# Schema.net
KiCad netlist of a schematic drawn in Altium Designer
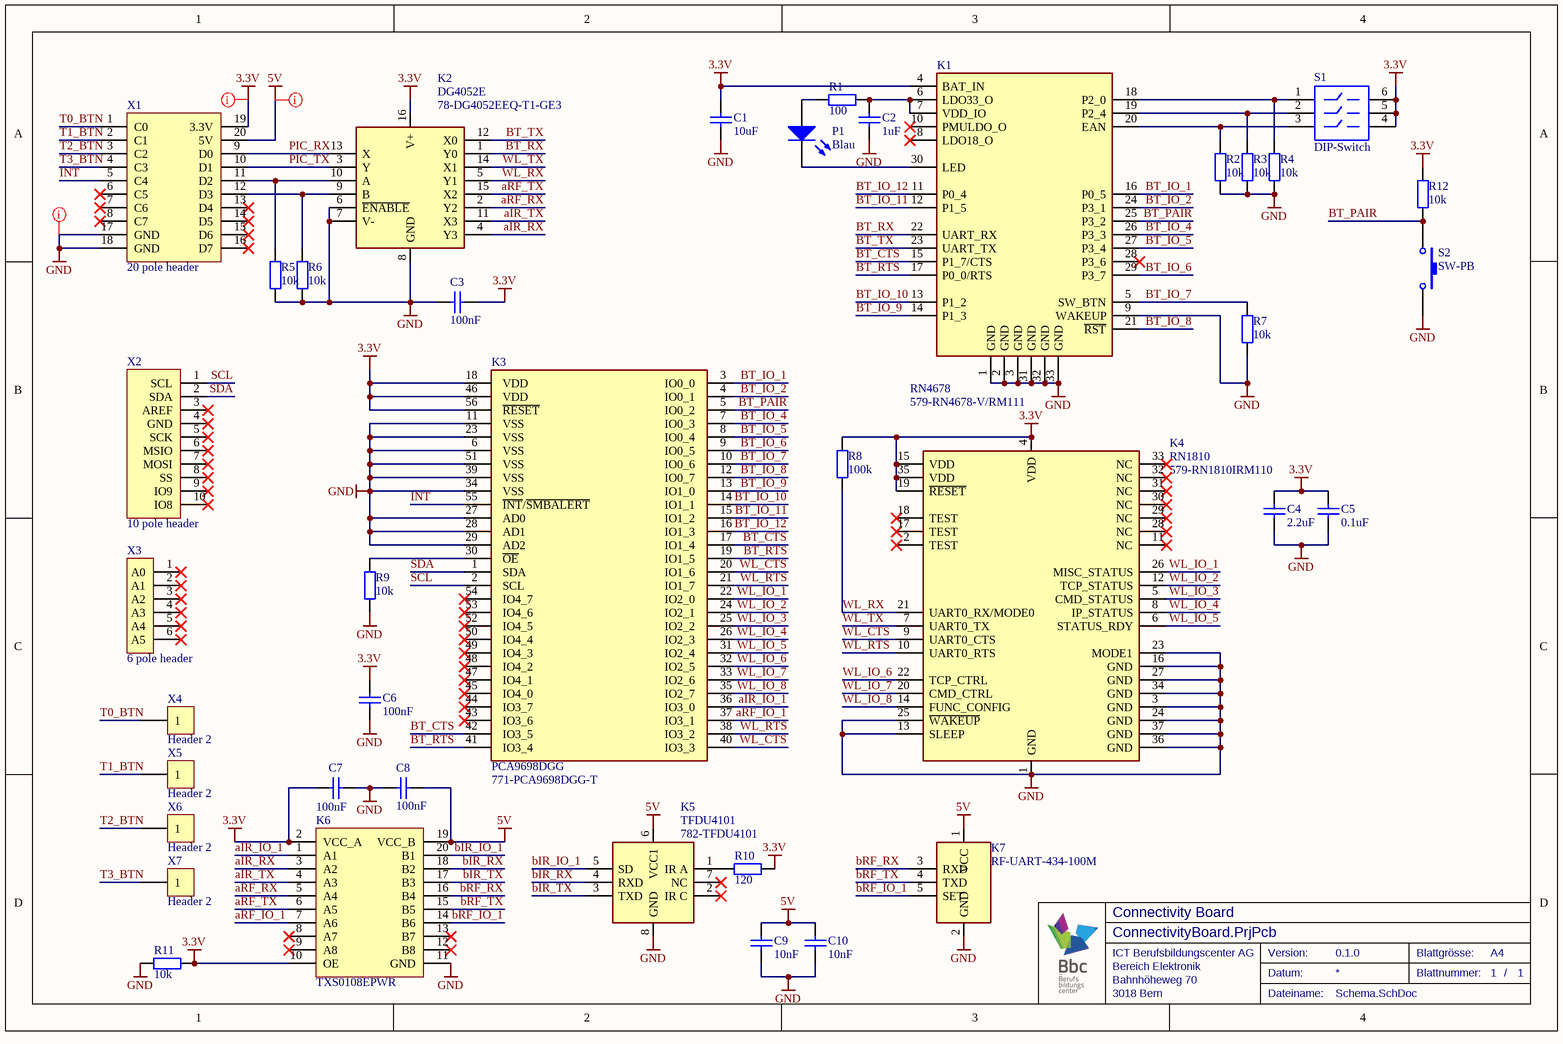
[diagram p0: Schema.SchDoc]

(export (version "E")
  (design (tool "Eeschema 10.0.6"))
  (components
    (comp (ref "C1")
      (value "10uF")
      (footprint "CAP CER 0805 H")
      (description "Non polarized capacitor")
      (fields (field (name "Comment") "Capacitor") (field (name "PUBLISHER") "ICT Berufsbildungscenter AG"))
      (libsource (lib "SchematicLibrary") (part "Capacitor"))
    )
    (comp (ref "C2")
      (value "1uF")
      (footprint "CAP CER 0805 H")
      (description "Non polarized capacitor")
      (fields (field (name "Comment") "Capacitor") (field (name "PUBLISHER") "ICT Berufsbildungscenter AG"))
      (libsource (lib "SchematicLibrary") (part "Capacitor"))
    )
    (comp (ref "C3")
      (value "100nF")
      (footprint "CAP CER 0805 H")
      (description "Non polarized capacitor")
      (fields (field (name "Comment") "Capacitor") (field (name "PUBLISHER") "ICT Berufsbildungscenter AG"))
      (libsource (lib "SchematicLibrary") (part "Capacitor"))
    )
    (comp (ref "C4")
      (value "2.2uF")
      (footprint "CAP CER 0805 H")
      (description "Non polarized capacitor")
      (fields (field (name "Comment") "Capacitor") (field (name "PUBLISHER") "ICT Berufsbildungscenter AG"))
      (libsource (lib "SchematicLibrary") (part "Capacitor"))
    )
    (comp (ref "C5")
      (value "0.1uF")
      (footprint "CAP CER 0805 H")
      (description "Non polarized capacitor")
      (fields (field (name "Comment") "Capacitor") (field (name "PUBLISHER") "ICT Berufsbildungscenter AG"))
      (libsource (lib "SchematicLibrary") (part "Capacitor"))
    )
    (comp (ref "C6")
      (value "100nF")
      (footprint "CAP CER 0805 H")
      (description "Non polarized capacitor")
      (fields (field (name "Comment") "Capacitor") (field (name "PUBLISHER") "ICT Berufsbildungscenter AG"))
      (libsource (lib "SchematicLibrary") (part "Capacitor"))
    )
    (comp (ref "C7")
      (value "100nF")
      (footprint "CAP CER 0805 H")
      (description "Non polarized capacitor")
      (fields (field (name "Comment") "Capacitor") (field (name "PUBLISHER") "ICT Berufsbildungscenter AG"))
      (libsource (lib "SchematicLibrary") (part "Capacitor"))
    )
    (comp (ref "C8")
      (value "100nF")
      (footprint "CAP CER 0805 H")
      (description "Non polarized capacitor")
      (fields (field (name "Comment") "Capacitor") (field (name "PUBLISHER") "ICT Berufsbildungscenter AG"))
      (libsource (lib "SchematicLibrary") (part "Capacitor"))
    )
    (comp (ref "C9")
      (value "10nF")
      (footprint "CAP CER 0805 H")
      (description "Non polarized capacitor")
      (fields (field (name "Comment") "Capacitor") (field (name "PUBLISHER") "ICT Berufsbildungscenter AG"))
      (libsource (lib "SchematicLibrary") (part "Capacitor"))
    )
    (comp (ref "C10")
      (value "10nF")
      (footprint "CAP CER 0805 H")
      (description "Non polarized capacitor")
      (fields (field (name "Comment") "Capacitor") (field (name "PUBLISHER") "ICT Berufsbildungscenter AG"))
      (libsource (lib "SchematicLibrary") (part "Capacitor"))
    )
    (comp (ref "K1")
      (value "RN4678")
      (footprint "RN4678 Bluetooth Modul")
      (fields (field (name "SUPPLIER PART NUMBER 1") "579-RN4678-V/RM111"))
      (libsource (lib "SchematicLibrary") (part "Bluetooth-Modul"))
    )
    (comp (ref "K2")
      (value "DG4052E")
      (footprint "TSSOP-16")
      (description "Analogschalter IC Dual 4 Ch Multiplxr Pd 450mW TSSOP-16")
      (fields (field (name "SUPPLIER PART NUMBER 1") "78-DG4052EEQ-T1-GE3"))
      (libsource (lib "SchematicLibrary") (part "AnalogSwitch"))
    )
    (comp (ref "K3")
      (value "PCA9698DGG")
      (footprint "TSSOP-56")
      (description "Schnittstelle - I/O-Erweiterer 40BT I2C FM+TPGPIO IN-RS-PU OE")
      (fields (field (name "SUPPLIER PART NUMBER 1") "771-PCA9698DGG-T"))
      (libsource (lib "SchematicLibrary") (part "PortExpander"))
    )
    (comp (ref "K4")
      (value "RN1810")
      (footprint "RN1810 WLAN")
      (description "WLAN-Module (802.11) On board WiFiWiFly UART and PCB antenna")
      (fields (field (name "SUPPLIER PART NUMBER 1") "579-RN1810IRM110"))
      (libsource (lib "SchematicLibrary") (part "WLAN-Modul"))
    )
    (comp (ref "K5")
      (value "TFDU4101")
      (footprint "TFDU4101 Infrarot Modul")
      (description "Infrarot-Transceiver SIR 115.2 kbits/s")
      (fields (field (name "SUPPLIER PART NUMBER 1") "782-TFDU4101"))
      (libsource (lib "SchematicLibrary") (part "Infrarot-Modul"))
    )
    (comp (ref "K6")
      (value "TXS0108EPWR")
      (footprint "TSSOP-20 H")
      (description "Level Shifter with internal pullups")
      (libsource (lib "BBC_Components") (part "TXS0108EPWR"))
    )
    (comp (ref "K7")
      (value "RF-UART-434-100M")
      (footprint "RF-UART-434-100M")
      (description "RF-Modul UART/TTL Interface 100M")
      (libsource (lib "SchematicLibrary") (part "RF-Modul"))
    )
    (comp (ref "P1")
      (value "Blau")
      (footprint "LED 1206 blue R")
      (description "Light emitting diode")
      (fields (field (name "PUBLISHER") "ICT Berufsbildungscenter AG"))
      (libsource (lib "SchematicLibrary") (part "LED"))
    )
    (comp (ref "R1")
      (value "100")
      (footprint "RES 0805 H")
      (description "Resistor")
      (fields (field (name "PUBLISHER") "ICT Berufsbildungscenter AG"))
      (libsource (lib "") (part "Resistor_1"))
    )
    (comp (ref "R2")
      (value "10k")
      (footprint "RES 0805 H")
      (description "Resistor")
      (fields (field (name "PUBLISHER") "ICT Berufsbildungscenter AG"))
      (libsource (lib "SchematicLibrary") (part "Resistor"))
    )
    (comp (ref "R3")
      (value "10k")
      (footprint "RES 0805 H")
      (description "Resistor")
      (fields (field (name "PUBLISHER") "ICT Berufsbildungscenter AG"))
      (libsource (lib "SchematicLibrary") (part "Resistor"))
    )
    (comp (ref "R4")
      (value "10k")
      (footprint "RES 0805 H")
      (description "Resistor")
      (fields (field (name "PUBLISHER") "ICT Berufsbildungscenter AG"))
      (libsource (lib "SchematicLibrary") (part "Resistor"))
    )
    (comp (ref "R5")
      (value "10k")
      (footprint "RES 0805 H")
      (description "Resistor")
      (fields (field (name "PUBLISHER") "ICT Berufsbildungscenter AG"))
      (libsource (lib "SchematicLibrary") (part "Resistor"))
    )
    (comp (ref "R6")
      (value "10k")
      (footprint "RES 0805 H")
      (description "Resistor")
      (fields (field (name "PUBLISHER") "ICT Berufsbildungscenter AG"))
      (libsource (lib "SchematicLibrary") (part "Resistor"))
    )
    (comp (ref "R7")
      (value "10k")
      (footprint "RES 0805 H")
      (description "Resistor")
      (fields (field (name "PUBLISHER") "ICT Berufsbildungscenter AG"))
      (libsource (lib "BBC_Components") (part "Resistor"))
    )
    (comp (ref "R8")
      (value "100k")
      (footprint "RES 0805 H")
      (description "Resistor")
      (fields (field (name "PUBLISHER") "ICT Berufsbildungscenter AG"))
      (libsource (lib "BBC_Components") (part "Resistor"))
    )
    (comp (ref "R9")
      (value "10k")
      (footprint "RES 0805 H")
      (description "Resistor")
      (fields (field (name "PUBLISHER") "ICT Berufsbildungscenter AG"))
      (libsource (lib "BBC_Components") (part "Resistor"))
    )
    (comp (ref "R10")
      (value "120")
      (footprint "RES 0805 H")
      (description "Resistor")
      (fields (field (name "PUBLISHER") "ICT Berufsbildungscenter AG"))
      (libsource (lib "") (part "Resistor_1"))
    )
    (comp (ref "R11")
      (value "10k")
      (footprint "RES 0805 H")
      (description "Resistor")
      (fields (field (name "PUBLISHER") "ICT Berufsbildungscenter AG"))
      (libsource (lib "") (part "Resistor_1"))
    )
    (comp (ref "R12")
      (value "10k")
      (footprint "RES 0805 H")
      (description "Resistor")
      (fields (field (name "PUBLISHER") "ICT Berufsbildungscenter AG"))
      (libsource (lib "SchematicLibrary") (part "Resistor"))
    )
    (comp (ref "S1")
      (value "DIP-Switch")
      (footprint "DIP Switch SMD 3 H")
      (description "Dip Switch with 3 switches")
      (fields (field (name "PUBLISHER") "ICT Berufsbildungscenter AG"))
      (libsource (lib "SchematicLibrary") (part "DIP-Switch 3"))
    )
    (comp (ref "S2")
      (value "SW-PB")
      (footprint "drucktaster")
      (description "Switch, SMD")
      (fields (field (name "PUBLISHER") "Altium Limited"))
      (libsource (lib "SchematicLibrary") (part "Drucktaster"))
    )
    (comp (ref "X1")
      (value "20 pole header")
      (footprint "Header THT male 2x10")
      (description "board to board header")
      (fields (field (name "PUBLISHER") "ICT Berufsbildungscenter AG"))
      (libsource (lib "SchematicLibrary") (part "Header 20"))
    )
    (comp (ref "X2")
      (value "10 pole header")
      (footprint "Header THT male 1x10")
      (description "board to board header")
      (fields (field (name "PUBLISHER") "ICT Berufsbildungscenter AG"))
      (libsource (lib "SchematicLibrary") (part "Header 10"))
    )
    (comp (ref "X3")
      (value "6 pole header")
      (footprint "Header THT male 1x6")
      (description "board to board header")
      (fields (field (name "PUBLISHER") "ICT Berufsbildungscenter AG"))
      (libsource (lib "SchematicLibrary") (part "Header 6"))
    )
    (comp (ref "X4")
      (value "Header 2")
      (footprint "TouchPads")
      (description "Header, 2-Pin")
      (fields (field (name "PUBLISHER") "Altium Limited"))
      (libsource (lib "SchematicLibrary") (part "Header 1"))
    )
    (comp (ref "X5")
      (value "Header 2")
      (footprint "TouchPads")
      (description "Header, 2-Pin")
      (fields (field (name "PUBLISHER") "Altium Limited"))
      (libsource (lib "SchematicLibrary") (part "Header 1"))
    )
    (comp (ref "X6")
      (value "Header 2")
      (footprint "TouchPads")
      (description "Header, 2-Pin")
      (fields (field (name "PUBLISHER") "Altium Limited"))
      (libsource (lib "SchematicLibrary") (part "Header 1"))
    )
    (comp (ref "X7")
      (value "Header 2")
      (footprint "TouchPads")
      (description "Header, 2-Pin")
      (fields (field (name "PUBLISHER") "Altium Limited"))
      (libsource (lib "SchematicLibrary") (part "Header 1"))
    )
  )
  (nets
    (net (code "1") (name "/BT_CTS") (class "Default")
      (node (ref "K1") (pin "15") (pinfunction "P1_7/CTS_15") (pintype "passive"))
      (node (ref "K3") (pin "17") (pinfunction "IO1_4_17") (pintype "passive"))
      (node (ref "K3") (pin "42") (pinfunction "IO3_5_42") (pintype "passive"))
    )
    (net (code "2") (name "/BT_IO_1") (class "Default")
      (node (ref "K1") (pin "16") (pinfunction "P0_5_16") (pintype "passive"))
      (node (ref "K3") (pin "3") (pinfunction "IO0_0_3") (pintype "passive"))
    )
    (net (code "3") (name "/BT_IO_2") (class "Default")
      (node (ref "K1") (pin "24") (pinfunction "P3_1_24") (pintype "passive"))
      (node (ref "K3") (pin "4") (pinfunction "IO0_1_4") (pintype "passive"))
    )
    (net (code "4") (name "/BT_IO_4") (class "Default")
      (node (ref "K1") (pin "26") (pinfunction "P3_3_26") (pintype "passive"))
      (node (ref "K3") (pin "7") (pinfunction "IO0_3_7") (pintype "passive"))
    )
    (net (code "5") (name "/BT_IO_5") (class "Default")
      (node (ref "K1") (pin "27") (pinfunction "P3_4_27") (pintype "passive"))
      (node (ref "K3") (pin "8") (pinfunction "IO0_4_8") (pintype "passive"))
    )
    (net (code "6") (name "/BT_IO_6") (class "Default")
      (node (ref "K1") (pin "29") (pinfunction "P3_7_29") (pintype "passive"))
      (node (ref "K3") (pin "9") (pinfunction "IO0_5_9") (pintype "passive"))
    )
    (net (code "7") (name "/BT_IO_7") (class "Default")
      (node (ref "K1") (pin "5") (pinfunction "SW_BTN_5") (pintype "passive"))
      (node (ref "K3") (pin "10") (pinfunction "IO0_6_10") (pintype "passive"))
      (node (ref "R7") (pin "2") (pinfunction "2_2") (pintype "passive"))
    )
    (net (code "8") (name "/BT_IO_8") (class "Default")
      (node (ref "K1") (pin "21") (pinfunction "~{RST}_21") (pintype "passive"))
      (node (ref "K3") (pin "12") (pinfunction "IO0_7_12") (pintype "passive"))
    )
    (net (code "9") (name "/BT_IO_9") (class "Default")
      (node (ref "K1") (pin "14") (pinfunction "P1_3_14") (pintype "passive"))
      (node (ref "K3") (pin "13") (pinfunction "IO1_0_13") (pintype "passive"))
    )
    (net (code "10") (name "/BT_IO_10") (class "Default")
      (node (ref "K1") (pin "13") (pinfunction "P1_2_13") (pintype "passive"))
      (node (ref "K3") (pin "14") (pinfunction "IO1_1_14") (pintype "passive"))
    )
    (net (code "11") (name "/BT_IO_11") (class "Default")
      (node (ref "K1") (pin "12") (pinfunction "P1_5_12") (pintype "passive"))
      (node (ref "K3") (pin "15") (pinfunction "IO1_2_15") (pintype "passive"))
    )
    (net (code "12") (name "/BT_IO_12") (class "Default")
      (node (ref "K1") (pin "11") (pinfunction "P0_4_11") (pintype "passive"))
      (node (ref "K3") (pin "16") (pinfunction "IO1_3_16") (pintype "passive"))
    )
    (net (code "13") (name "/BT_PAIR") (class "Default")
      (node (ref "K1") (pin "25") (pinfunction "P3_2_25") (pintype "passive"))
      (node (ref "K3") (pin "5") (pinfunction "IO0_2_5") (pintype "passive"))
      (node (ref "R12") (pin "1") (pinfunction "1_1") (pintype "passive"))
      (node (ref "S2") (pin "4") (pinfunction "4_4") (pintype "passive"))
    )
    (net (code "14") (name "/BT_RTS") (class "Default")
      (node (ref "K1") (pin "17") (pinfunction "P0_0/RTS_17") (pintype "passive"))
      (node (ref "K3") (pin "19") (pinfunction "IO1_5_19") (pintype "passive"))
      (node (ref "K3") (pin "41") (pinfunction "IO3_4_41") (pintype "passive"))
    )
    (net (code "15") (name "/BT_RX") (class "Default")
      (node (ref "K1") (pin "22") (pinfunction "UART_RX_22") (pintype "passive"))
      (node (ref "K2") (pin "1") (pinfunction "Y0_1") (pintype "passive"))
    )
    (net (code "16") (name "/BT_TX") (class "Default")
      (node (ref "K1") (pin "23") (pinfunction "UART_TX_23") (pintype "passive"))
      (node (ref "K2") (pin "12") (pinfunction "X0_12") (pintype "passive"))
    )
    (net (code "17") (name "/PIC_RX") (class "Default")
      (node (ref "K2") (pin "13") (pinfunction "X_13") (pintype "passive"))
      (node (ref "X1") (pin "9") (pinfunction "D0_9") (pintype "passive"))
    )
    (net (code "18") (name "/PIC_TX") (class "Default")
      (node (ref "K2") (pin "3") (pinfunction "Y_3") (pintype "passive"))
      (node (ref "X1") (pin "10") (pinfunction "D1_10") (pintype "passive"))
    )
    (net (code "19") (name "/SCL") (class "Default")
      (node (ref "K3") (pin "2") (pinfunction "SCL_2") (pintype "passive"))
      (node (ref "X2") (pin "1") (pinfunction "SCL_1") (pintype "passive"))
    )
    (net (code "20") (name "/SDA") (class "Default")
      (node (ref "K3") (pin "1") (pinfunction "SDA_1") (pintype "passive"))
      (node (ref "X2") (pin "2") (pinfunction "SDA_2") (pintype "passive"))
    )
    (net (code "21") (name "/T0_BTN") (class "Default")
      (node (ref "X1") (pin "1") (pinfunction "C0_1") (pintype "passive"))
      (node (ref "X4") (pin "1") (pinfunction "1_1") (pintype "passive"))
    )
    (net (code "22") (name "/T1_BTN") (class "Default")
      (node (ref "X1") (pin "2") (pinfunction "C1_2") (pintype "passive"))
      (node (ref "X5") (pin "1") (pinfunction "1_1") (pintype "passive"))
    )
    (net (code "23") (name "/T2_BTN") (class "Default")
      (node (ref "X1") (pin "3") (pinfunction "C2_3") (pintype "passive"))
      (node (ref "X6") (pin "1") (pinfunction "1_1") (pintype "passive"))
    )
    (net (code "24") (name "/T3_BTN") (class "Default")
      (node (ref "X1") (pin "4") (pinfunction "C3_4") (pintype "passive"))
      (node (ref "X7") (pin "1") (pinfunction "1_1") (pintype "passive"))
    )
    (net (code "25") (name "/WL_CTS") (class "Default")
      (node (ref "K3") (pin "20") (pinfunction "IO1_6_20") (pintype "passive"))
      (node (ref "K3") (pin "40") (pinfunction "IO3_3_40") (pintype "passive"))
      (node (ref "K4") (pin "9") (pinfunction "UART0_CTS_9") (pintype "passive"))
    )
    (net (code "26") (name "/WL_IO_1") (class "Default")
      (node (ref "K3") (pin "22") (pinfunction "IO2_0_22") (pintype "passive"))
      (node (ref "K4") (pin "26") (pinfunction "MISC_STATUS_26") (pintype "passive"))
    )
    (net (code "27") (name "/WL_IO_2") (class "Default")
      (node (ref "K3") (pin "24") (pinfunction "IO2_1_24") (pintype "passive"))
      (node (ref "K4") (pin "12") (pinfunction "TCP_STATUS_12") (pintype "passive"))
    )
    (net (code "28") (name "/WL_IO_3") (class "Default")
      (node (ref "K3") (pin "25") (pinfunction "IO2_2_25") (pintype "passive"))
      (node (ref "K4") (pin "5") (pinfunction "CMD_STATUS_5") (pintype "passive"))
    )
    (net (code "29") (name "/WL_IO_4") (class "Default")
      (node (ref "K3") (pin "26") (pinfunction "IO2_3_26") (pintype "passive"))
      (node (ref "K4") (pin "8") (pinfunction "IP_STATUS_8") (pintype "passive"))
    )
    (net (code "30") (name "/WL_IO_5") (class "Default")
      (node (ref "K3") (pin "31") (pinfunction "IO2_4_31") (pintype "passive"))
      (node (ref "K4") (pin "6") (pinfunction "STATUS_RDY_6") (pintype "passive"))
    )
    (net (code "31") (name "/WL_IO_6") (class "Default")
      (node (ref "K3") (pin "32") (pinfunction "IO2_5_32") (pintype "passive"))
      (node (ref "K4") (pin "22") (pinfunction "TCP_CTRL_22") (pintype "passive"))
    )
    (net (code "32") (name "/WL_IO_7") (class "Default")
      (node (ref "K3") (pin "33") (pinfunction "IO2_6_33") (pintype "passive"))
      (node (ref "K4") (pin "20") (pinfunction "CMD_CTRL_20") (pintype "passive"))
    )
    (net (code "33") (name "/WL_IO_8") (class "Default")
      (node (ref "K3") (pin "35") (pinfunction "IO2_7_35") (pintype "passive"))
      (node (ref "K4") (pin "14") (pinfunction "FUNC_CONFIG_14") (pintype "passive"))
    )
    (net (code "34") (name "/WL_RTS") (class "Default")
      (node (ref "K3") (pin "21") (pinfunction "IO1_7_21") (pintype "passive"))
      (node (ref "K3") (pin "38") (pinfunction "IO3_2_38") (pintype "passive"))
      (node (ref "K4") (pin "10") (pinfunction "UART0_RTS_10") (pintype "passive"))
    )
    (net (code "35") (name "/WL_RX") (class "Default")
      (node (ref "K2") (pin "5") (pinfunction "Y1_5") (pintype "passive"))
      (node (ref "K4") (pin "21") (pinfunction "UART0_RX/MODE0_21") (pintype "passive"))
      (node (ref "R8") (pin "1") (pinfunction "1_1") (pintype "passive"))
    )
    (net (code "36") (name "/WL_TX") (class "Default")
      (node (ref "K2") (pin "14") (pinfunction "X1_14") (pintype "passive"))
      (node (ref "K4") (pin "7") (pinfunction "UART0_TX_7") (pintype "passive"))
    )
    (net (code "37") (name "/aIR_IO_1") (class "Default")
      (node (ref "K3") (pin "36") (pinfunction "IO3_0_36") (pintype "passive"))
      (node (ref "K6") (pin "1") (pinfunction "A1_1") (pintype "passive"))
    )
    (net (code "38") (name "/aIR_RX") (class "Default")
      (node (ref "K2") (pin "4") (pinfunction "Y3_4") (pintype "passive"))
      (node (ref "K6") (pin "3") (pinfunction "A2_3") (pintype "passive"))
    )
    (net (code "39") (name "/aIR_TX") (class "Default")
      (node (ref "K2") (pin "11") (pinfunction "X3_11") (pintype "passive"))
      (node (ref "K6") (pin "4") (pinfunction "A3_4") (pintype "passive"))
    )
    (net (code "40") (name "/aRF_IO_1") (class "Default")
      (node (ref "K3") (pin "37") (pinfunction "IO3_1_37") (pintype "passive"))
      (node (ref "K6") (pin "7") (pinfunction "A6_7") (pintype "passive"))
    )
    (net (code "41") (name "/aRF_RX") (class "Default")
      (node (ref "K2") (pin "2") (pinfunction "Y2_2") (pintype "passive"))
      (node (ref "K6") (pin "5") (pinfunction "A4_5") (pintype "passive"))
    )
    (net (code "42") (name "/aRF_TX") (class "Default")
      (node (ref "K2") (pin "15") (pinfunction "X2_15") (pintype "passive"))
      (node (ref "K6") (pin "6") (pinfunction "A5_6") (pintype "passive"))
    )
    (net (code "43") (name "/bIR_IO_1") (class "Default")
      (node (ref "K5") (pin "5") (pinfunction "SD_5") (pintype "passive"))
      (node (ref "K6") (pin "20") (pinfunction "B1_20") (pintype "passive"))
    )
    (net (code "44") (name "/bIR_RX") (class "Default")
      (node (ref "K5") (pin "4") (pinfunction "RXD_4") (pintype "passive"))
      (node (ref "K6") (pin "18") (pinfunction "B2_18") (pintype "passive"))
    )
    (net (code "45") (name "/bIR_TX") (class "Default")
      (node (ref "K5") (pin "3") (pinfunction "TXD_3") (pintype "passive"))
      (node (ref "K6") (pin "17") (pinfunction "B3_17") (pintype "passive"))
    )
    (net (code "46") (name "/bRF_IO_1") (class "Default")
      (node (ref "K6") (pin "14") (pinfunction "B6_14") (pintype "passive"))
      (node (ref "K7") (pin "5") (pinfunction "SET_5") (pintype "passive"))
    )
    (net (code "47") (name "/bRF_RX") (class "Default")
      (node (ref "K6") (pin "16") (pinfunction "B4_16") (pintype "passive"))
      (node (ref "K7") (pin "3") (pinfunction "RXD_3") (pintype "passive"))
    )
    (net (code "48") (name "/bRF_TX") (class "Default")
      (node (ref "K6") (pin "15") (pinfunction "B5_15") (pintype "passive"))
      (node (ref "K7") (pin "4") (pinfunction "TXD_4") (pintype "passive"))
    )
    (net (code "49") (name "/~{INT}") (class "Default")
      (node (ref "K3") (pin "55") (pinfunction "~{INT}/~{SMBALERT}_55") (pintype "passive"))
      (node (ref "X1") (pin "5") (pinfunction "C4_5") (pintype "passive"))
    )
    (net (code "50") (name "3.3V") (class "Default")
      (node (ref "C1") (pin "2") (pinfunction "2_2") (pintype "passive"))
      (node (ref "C3") (pin "2") (pinfunction "2_2") (pintype "passive"))
      (node (ref "C4") (pin "2") (pinfunction "2_2") (pintype "passive"))
      (node (ref "C5") (pin "2") (pinfunction "2_2") (pintype "passive"))
      (node (ref "C6") (pin "2") (pinfunction "2_2") (pintype "passive"))
      (node (ref "C7") (pin "1") (pinfunction "1_1") (pintype "passive"))
      (node (ref "K1") (pin "4") (pinfunction "BAT_IN_4") (pintype "passive"))
      (node (ref "K2") (pin "16") (pinfunction "V+_16") (pintype "passive"))
      (node (ref "K3") (pin "18") (pinfunction "VDD_18") (pintype "passive"))
      (node (ref "K3") (pin "46") (pinfunction "VDD_46") (pintype "passive"))
      (node (ref "K3") (pin "56") (pinfunction "~{RESET}_56") (pintype "passive"))
      (node (ref "K4") (pin "15") (pinfunction "VDD_15") (pintype "passive"))
      (node (ref "K4") (pin "19") (pinfunction "~{RESET}_19") (pintype "passive"))
      (node (ref "K4") (pin "35") (pinfunction "VDD_35") (pintype "passive"))
      (node (ref "K4") (pin "4") (pinfunction "VDD_4") (pintype "passive"))
      (node (ref "K6") (pin "10") (pinfunction "OE_10") (pintype "passive"))
      (node (ref "K6") (pin "2") (pinfunction "VCC_A_2") (pintype "passive"))
      (node (ref "R10") (pin "2") (pinfunction "2_2") (pintype "passive"))
      (node (ref "R11") (pin "2") (pinfunction "2_2") (pintype "passive"))
      (node (ref "R12") (pin "2") (pinfunction "2_2") (pintype "passive"))
      (node (ref "R8") (pin "2") (pinfunction "2_2") (pintype "passive"))
      (node (ref "S1") (pin "4") (pinfunction "4_4") (pintype "passive"))
      (node (ref "S1") (pin "5") (pinfunction "5_5") (pintype "passive"))
      (node (ref "S1") (pin "6") (pinfunction "6_6") (pintype "passive"))
      (node (ref "X1") (pin "19") (pinfunction "3.3V_19") (pintype "passive"))
    )
    (net (code "51") (name "5V") (class "Default")
      (node (ref "C10") (pin "1") (pinfunction "1_1") (pintype "passive"))
      (node (ref "C8") (pin "2") (pinfunction "2_2") (pintype "passive"))
      (node (ref "C9") (pin "1") (pinfunction "1_1") (pintype "passive"))
      (node (ref "K5") (pin "6") (pinfunction "VCC1_6") (pintype "passive"))
      (node (ref "K6") (pin "19") (pinfunction "VCC_B_19") (pintype "passive"))
      (node (ref "K7") (pin "1") (pinfunction "VCC_1") (pintype "passive"))
      (node (ref "X1") (pin "20") (pinfunction "5V_20") (pintype "passive"))
    )
    (net (code "52") (name "GND") (class "Default")
      (node (ref "C1") (pin "1") (pinfunction "1_1") (pintype "passive"))
      (node (ref "C10") (pin "2") (pinfunction "2_2") (pintype "passive"))
      (node (ref "C2") (pin "1") (pinfunction "1_1") (pintype "passive"))
      (node (ref "C3") (pin "1") (pinfunction "1_1") (pintype "passive"))
      (node (ref "C4") (pin "1") (pinfunction "1_1") (pintype "passive"))
      (node (ref "C5") (pin "1") (pinfunction "1_1") (pintype "passive"))
      (node (ref "C6") (pin "1") (pinfunction "1_1") (pintype "passive"))
      (node (ref "C7") (pin "2") (pinfunction "2_2") (pintype "passive"))
      (node (ref "C8") (pin "1") (pinfunction "1_1") (pintype "passive"))
      (node (ref "C9") (pin "2") (pinfunction "2_2") (pintype "passive"))
      (node (ref "K1") (pin "1") (pinfunction "GND_1") (pintype "passive"))
      (node (ref "K1") (pin "2") (pinfunction "GND_2") (pintype "passive"))
      (node (ref "K1") (pin "3") (pinfunction "GND_3") (pintype "passive"))
      (node (ref "K1") (pin "31") (pinfunction "GND_31") (pintype "passive"))
      (node (ref "K1") (pin "32") (pinfunction "GND_32") (pintype "passive"))
      (node (ref "K1") (pin "33") (pinfunction "GND_33") (pintype "passive"))
      (node (ref "K1") (pin "9") (pinfunction "WAKEUP_9") (pintype "passive"))
      (node (ref "K2") (pin "6") (pinfunction "~{ENABLE}_6") (pintype "passive"))
      (node (ref "K2") (pin "7") (pinfunction "V-_7") (pintype "passive"))
      (node (ref "K2") (pin "8") (pinfunction "GND_8") (pintype "passive"))
      (node (ref "K3") (pin "11") (pinfunction "VSS_11") (pintype "passive"))
      (node (ref "K3") (pin "23") (pinfunction "VSS_23") (pintype "passive"))
      (node (ref "K3") (pin "27") (pinfunction "AD0_27") (pintype "passive"))
      (node (ref "K3") (pin "28") (pinfunction "AD1_28") (pintype "passive"))
      (node (ref "K3") (pin "29") (pinfunction "AD2_29") (pintype "passive"))
      (node (ref "K3") (pin "34") (pinfunction "VSS_34") (pintype "passive"))
      (node (ref "K3") (pin "39") (pinfunction "VSS_39") (pintype "passive"))
      (node (ref "K3") (pin "51") (pinfunction "VSS_51") (pintype "passive"))
      (node (ref "K3") (pin "6") (pinfunction "VSS_6") (pintype "passive"))
      (node (ref "K4") (pin "1") (pinfunction "GND_1") (pintype "passive"))
      (node (ref "K4") (pin "13") (pinfunction "SLEEP_13") (pintype "passive"))
      (node (ref "K4") (pin "16") (pinfunction "GND_16") (pintype "passive"))
      (node (ref "K4") (pin "23") (pinfunction "MODE1_23") (pintype "passive"))
      (node (ref "K4") (pin "24") (pinfunction "GND_24") (pintype "passive"))
      (node (ref "K4") (pin "25") (pinfunction "~{WAKEUP}_25") (pintype "passive"))
      (node (ref "K4") (pin "27") (pinfunction "GND_27") (pintype "passive"))
      (node (ref "K4") (pin "3") (pinfunction "GND_3") (pintype "passive"))
      (node (ref "K4") (pin "34") (pinfunction "GND_34") (pintype "passive"))
      (node (ref "K4") (pin "36") (pinfunction "GND_36") (pintype "passive"))
      (node (ref "K4") (pin "37") (pinfunction "GND_37") (pintype "passive"))
      (node (ref "K5") (pin "8") (pinfunction "GND_8") (pintype "passive"))
      (node (ref "K6") (pin "11") (pinfunction "GND_11") (pintype "passive"))
      (node (ref "K7") (pin "2") (pinfunction "GND_2") (pintype "passive"))
      (node (ref "R11") (pin "1") (pinfunction "1_1") (pintype "passive"))
      (node (ref "R2") (pin "1") (pinfunction "1_1") (pintype "passive"))
      (node (ref "R3") (pin "1") (pinfunction "1_1") (pintype "passive"))
      (node (ref "R4") (pin "1") (pinfunction "1_1") (pintype "passive"))
      (node (ref "R5") (pin "1") (pinfunction "1_1") (pintype "passive"))
      (node (ref "R6") (pin "1") (pinfunction "1_1") (pintype "passive"))
      (node (ref "R7") (pin "1") (pinfunction "1_1") (pintype "passive"))
      (node (ref "R9") (pin "1") (pinfunction "1_1") (pintype "passive"))
      (node (ref "S2") (pin "1") (pinfunction "1_1") (pintype "passive"))
      (node (ref "X1") (pin "17") (pinfunction "GND_17") (pintype "passive"))
      (node (ref "X1") (pin "18") (pinfunction "GND_18") (pintype "passive"))
    )
    (net (code "53") (name "Net-(K1-EAN)") (class "Default")
      (node (ref "K1") (pin "20") (pinfunction "EAN_20") (pintype "passive"))
      (node (ref "R2") (pin "2") (pinfunction "2_2") (pintype "passive"))
      (node (ref "S1") (pin "3") (pinfunction "3_3") (pintype "passive"))
    )
    (net (code "54") (name "Net-(K1-LDO33_O)") (class "Default")
      (node (ref "C2") (pin "2") (pinfunction "2_2") (pintype "passive"))
      (node (ref "K1") (pin "6") (pinfunction "LDO33_O_6") (pintype "passive"))
      (node (ref "K1") (pin "7") (pinfunction "VDD_IO_7") (pintype "passive"))
      (node (ref "R1") (pin "2") (pinfunction "2_2") (pintype "passive"))
    )
    (net (code "55") (name "Net-(K1-LED)") (class "Default")
      (node (ref "K1") (pin "30") (pinfunction "LED_30") (pintype "passive"))
      (node (ref "P1") (pin "C") (pinfunction "Cathode_C") (pintype "passive"))
    )
    (net (code "56") (name "Net-(K1-P2_0)") (class "Default")
      (node (ref "K1") (pin "18") (pinfunction "P2_0_18") (pintype "passive"))
      (node (ref "R4") (pin "2") (pinfunction "2_2") (pintype "passive"))
      (node (ref "S1") (pin "1") (pinfunction "1_1") (pintype "passive"))
    )
    (net (code "57") (name "Net-(K1-P2_4)") (class "Default")
      (node (ref "K1") (pin "19") (pinfunction "P2_4_19") (pintype "passive"))
      (node (ref "R3") (pin "2") (pinfunction "2_2") (pintype "passive"))
      (node (ref "S1") (pin "2") (pinfunction "2_2") (pintype "passive"))
    )
    (net (code "58") (name "Net-(K2-A)") (class "Default")
      (node (ref "K2") (pin "10") (pinfunction "A_10") (pintype "passive"))
      (node (ref "R5") (pin "2") (pinfunction "2_2") (pintype "passive"))
      (node (ref "X1") (pin "11") (pinfunction "D2_11") (pintype "passive"))
    )
    (net (code "59") (name "Net-(K2-B)") (class "Default")
      (node (ref "K2") (pin "9") (pinfunction "B_9") (pintype "passive"))
      (node (ref "R6") (pin "2") (pinfunction "2_2") (pintype "passive"))
      (node (ref "X1") (pin "12") (pinfunction "D3_12") (pintype "passive"))
    )
    (net (code "60") (name "Net-(K3-~{OE})") (class "Default")
      (node (ref "K3") (pin "30") (pinfunction "~{OE}_30") (pintype "passive"))
      (node (ref "R9") (pin "2") (pinfunction "2_2") (pintype "passive"))
    )
    (net (code "61") (name "Net-(K5-IR_A)") (class "Default")
      (node (ref "K5") (pin "1") (pinfunction "IR_A_1") (pintype "passive"))
      (node (ref "R10") (pin "1") (pinfunction "1_1") (pintype "passive"))
    )
    (net (code "62") (name "Net-(P1-Anode)") (class "Default")
      (node (ref "P1") (pin "A") (pinfunction "Anode_A") (pintype "passive"))
      (node (ref "R1") (pin "1") (pinfunction "1_1") (pintype "passive"))
    )
    (net (code "63") (name "unconnected-(K1-LDO18_O-Pad8)") (class "Default")
      (node (ref "K1") (pin "8") (pinfunction "LDO18_O_8") (pintype "passive+no_connect"))
    )
    (net (code "64") (name "unconnected-(K1-P3_6-Pad28)") (class "Default")
      (node (ref "K1") (pin "28") (pinfunction "P3_6_28") (pintype "passive+no_connect"))
    )
    (net (code "65") (name "unconnected-(K1-PMULDO_O-Pad10)") (class "Default")
      (node (ref "K1") (pin "10") (pinfunction "PMULDO_O_10") (pintype "passive+no_connect"))
    )
    (net (code "66") (name "unconnected-(K3-IO3_6-Pad43)") (class "Default")
      (node (ref "K3") (pin "43") (pinfunction "IO3_6_43") (pintype "passive+no_connect"))
    )
    (net (code "67") (name "unconnected-(K3-IO3_7-Pad44)") (class "Default")
      (node (ref "K3") (pin "44") (pinfunction "IO3_7_44") (pintype "passive+no_connect"))
    )
    (net (code "68") (name "unconnected-(K3-IO4_0-Pad45)") (class "Default")
      (node (ref "K3") (pin "45") (pinfunction "IO4_0_45") (pintype "passive+no_connect"))
    )
    (net (code "69") (name "unconnected-(K3-IO4_1-Pad47)") (class "Default")
      (node (ref "K3") (pin "47") (pinfunction "IO4_1_47") (pintype "passive+no_connect"))
    )
    (net (code "70") (name "unconnected-(K3-IO4_2-Pad48)") (class "Default")
      (node (ref "K3") (pin "48") (pinfunction "IO4_2_48") (pintype "passive+no_connect"))
    )
    (net (code "71") (name "unconnected-(K3-IO4_3-Pad49)") (class "Default")
      (node (ref "K3") (pin "49") (pinfunction "IO4_3_49") (pintype "passive+no_connect"))
    )
    (net (code "72") (name "unconnected-(K3-IO4_4-Pad50)") (class "Default")
      (node (ref "K3") (pin "50") (pinfunction "IO4_4_50") (pintype "passive+no_connect"))
    )
    (net (code "73") (name "unconnected-(K3-IO4_5-Pad52)") (class "Default")
      (node (ref "K3") (pin "52") (pinfunction "IO4_5_52") (pintype "passive+no_connect"))
    )
    (net (code "74") (name "unconnected-(K3-IO4_6-Pad53)") (class "Default")
      (node (ref "K3") (pin "53") (pinfunction "IO4_6_53") (pintype "passive+no_connect"))
    )
    (net (code "75") (name "unconnected-(K3-IO4_7-Pad54)") (class "Default")
      (node (ref "K3") (pin "54") (pinfunction "IO4_7_54") (pintype "passive+no_connect"))
    )
    (net (code "76") (name "unconnected-(K4-NC-Pad11)") (class "Default")
      (node (ref "K4") (pin "11") (pinfunction "NC_11") (pintype "passive+no_connect"))
    )
    (net (code "77") (name "unconnected-(K4-NC-Pad28)") (class "Default")
      (node (ref "K4") (pin "28") (pinfunction "NC_28") (pintype "passive+no_connect"))
    )
    (net (code "78") (name "unconnected-(K4-NC-Pad29)") (class "Default")
      (node (ref "K4") (pin "29") (pinfunction "NC_29") (pintype "passive+no_connect"))
    )
    (net (code "79") (name "unconnected-(K4-NC-Pad30)") (class "Default")
      (node (ref "K4") (pin "30") (pinfunction "NC_30") (pintype "passive+no_connect"))
    )
    (net (code "80") (name "unconnected-(K4-NC-Pad31)") (class "Default")
      (node (ref "K4") (pin "31") (pinfunction "NC_31") (pintype "passive+no_connect"))
    )
    (net (code "81") (name "unconnected-(K4-NC-Pad32)") (class "Default")
      (node (ref "K4") (pin "32") (pinfunction "NC_32") (pintype "passive+no_connect"))
    )
    (net (code "82") (name "unconnected-(K4-NC-Pad33)") (class "Default")
      (node (ref "K4") (pin "33") (pinfunction "NC_33") (pintype "passive+no_connect"))
    )
    (net (code "83") (name "unconnected-(K4-TEST-Pad2)") (class "Default")
      (node (ref "K4") (pin "2") (pinfunction "TEST_2") (pintype "passive+no_connect"))
    )
    (net (code "84") (name "unconnected-(K4-TEST-Pad17)") (class "Default")
      (node (ref "K4") (pin "17") (pinfunction "TEST_17") (pintype "passive+no_connect"))
    )
    (net (code "85") (name "unconnected-(K4-TEST-Pad18)") (class "Default")
      (node (ref "K4") (pin "18") (pinfunction "TEST_18") (pintype "passive+no_connect"))
    )
    (net (code "86") (name "unconnected-(K5-IR_C-Pad2)") (class "Default")
      (node (ref "K5") (pin "2") (pinfunction "IR_C_2") (pintype "passive+no_connect"))
    )
    (net (code "87") (name "unconnected-(K5-NC-Pad7)") (class "Default")
      (node (ref "K5") (pin "7") (pinfunction "NC_7") (pintype "passive+no_connect"))
    )
    (net (code "88") (name "unconnected-(K6-A7-Pad8)") (class "Default")
      (node (ref "K6") (pin "8") (pinfunction "A7_8") (pintype "passive+no_connect"))
    )
    (net (code "89") (name "unconnected-(K6-A8-Pad9)") (class "Default")
      (node (ref "K6") (pin "9") (pinfunction "A8_9") (pintype "passive+no_connect"))
    )
    (net (code "90") (name "unconnected-(K6-B7-Pad13)") (class "Default")
      (node (ref "K6") (pin "13") (pinfunction "B7_13") (pintype "passive+no_connect"))
    )
    (net (code "91") (name "unconnected-(K6-B8-Pad12)") (class "Default")
      (node (ref "K6") (pin "12") (pinfunction "B8_12") (pintype "passive+no_connect"))
    )
    (net (code "92") (name "unconnected-(X1-C5-Pad6)") (class "Default")
      (node (ref "X1") (pin "6") (pinfunction "C5_6") (pintype "passive+no_connect"))
    )
    (net (code "93") (name "unconnected-(X1-C6-Pad7)") (class "Default")
      (node (ref "X1") (pin "7") (pinfunction "C6_7") (pintype "passive+no_connect"))
    )
    (net (code "94") (name "unconnected-(X1-C7-Pad8)") (class "Default")
      (node (ref "X1") (pin "8") (pinfunction "C7_8") (pintype "passive+no_connect"))
    )
    (net (code "95") (name "unconnected-(X1-D4-Pad13)") (class "Default")
      (node (ref "X1") (pin "13") (pinfunction "D4_13") (pintype "passive+no_connect"))
    )
    (net (code "96") (name "unconnected-(X1-D5-Pad14)") (class "Default")
      (node (ref "X1") (pin "14") (pinfunction "D5_14") (pintype "passive+no_connect"))
    )
    (net (code "97") (name "unconnected-(X1-D6-Pad15)") (class "Default")
      (node (ref "X1") (pin "15") (pinfunction "D6_15") (pintype "passive+no_connect"))
    )
    (net (code "98") (name "unconnected-(X1-D7-Pad16)") (class "Default")
      (node (ref "X1") (pin "16") (pinfunction "D7_16") (pintype "passive+no_connect"))
    )
    (net (code "99") (name "unconnected-(X2-AREF-Pad3)") (class "Default")
      (node (ref "X2") (pin "3") (pinfunction "AREF_3") (pintype "passive+no_connect"))
    )
    (net (code "100") (name "unconnected-(X2-GND-Pad4)") (class "Default")
      (node (ref "X2") (pin "4") (pinfunction "GND_4") (pintype "passive+no_connect"))
    )
    (net (code "101") (name "unconnected-(X2-IO8-Pad10)") (class "Default")
      (node (ref "X2") (pin "10") (pinfunction "IO8_10") (pintype "passive+no_connect"))
    )
    (net (code "102") (name "unconnected-(X2-IO9-Pad9)") (class "Default")
      (node (ref "X2") (pin "9") (pinfunction "IO9_9") (pintype "passive+no_connect"))
    )
    (net (code "103") (name "unconnected-(X2-MOSI-Pad7)") (class "Default")
      (node (ref "X2") (pin "7") (pinfunction "MOSI_7") (pintype "passive+no_connect"))
    )
    (net (code "104") (name "unconnected-(X2-MSIO-Pad6)") (class "Default")
      (node (ref "X2") (pin "6") (pinfunction "MSIO_6") (pintype "passive+no_connect"))
    )
    (net (code "105") (name "unconnected-(X2-SCK-Pad5)") (class "Default")
      (node (ref "X2") (pin "5") (pinfunction "SCK_5") (pintype "passive+no_connect"))
    )
    (net (code "106") (name "unconnected-(X2-SS-Pad8)") (class "Default")
      (node (ref "X2") (pin "8") (pinfunction "SS_8") (pintype "passive+no_connect"))
    )
    (net (code "107") (name "unconnected-(X3-A0-Pad1)") (class "Default")
      (node (ref "X3") (pin "1") (pinfunction "A0_1") (pintype "passive+no_connect"))
    )
    (net (code "108") (name "unconnected-(X3-A1-Pad2)") (class "Default")
      (node (ref "X3") (pin "2") (pinfunction "A1_2") (pintype "passive+no_connect"))
    )
    (net (code "109") (name "unconnected-(X3-A2-Pad3)") (class "Default")
      (node (ref "X3") (pin "3") (pinfunction "A2_3") (pintype "passive+no_connect"))
    )
    (net (code "110") (name "unconnected-(X3-A3-Pad4)") (class "Default")
      (node (ref "X3") (pin "4") (pinfunction "A3_4") (pintype "passive+no_connect"))
    )
    (net (code "111") (name "unconnected-(X3-A4-Pad5)") (class "Default")
      (node (ref "X3") (pin "5") (pinfunction "A4_5") (pintype "passive+no_connect"))
    )
    (net (code "112") (name "unconnected-(X3-A5-Pad6)") (class "Default")
      (node (ref "X3") (pin "6") (pinfunction "A5_6") (pintype "passive+no_connect"))
    )
  )
)
